# CATS_GS-Radio_MCU.net
KiCad netlist of a schematic drawn in Altium Designer
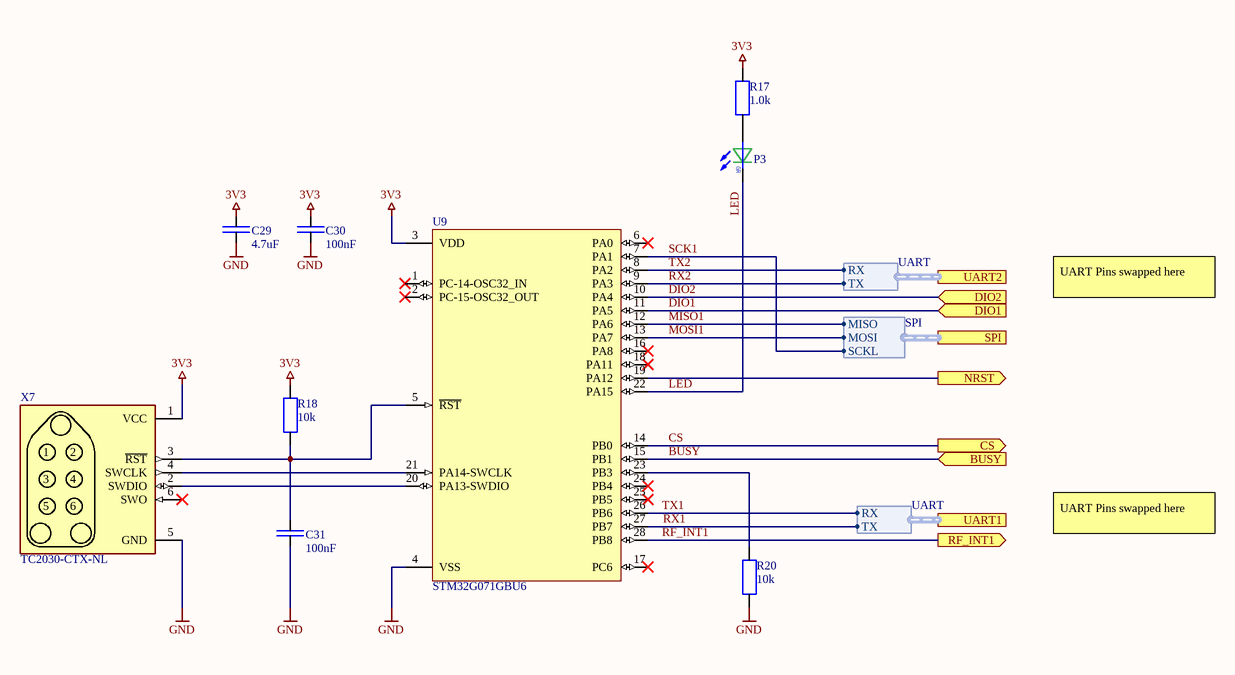
[diagram p0: CATS_GS-Radio_MCU.SchDoc]

(export (version "E")
  (design (tool "Eeschema 10.0.6"))
  (components
    (comp (ref "C29")
      (value "4.7uF")
      (footprint "SMD Keramikkondensator 0402")
      (description "SMD Ceramic Capacitor E6")
      (libsource (lib "CATS-EUROC") (part "E6 - 4.7uF"))
    )
    (comp (ref "C30")
      (value "100nF")
      (footprint "SMD Keramikkondensator 0402")
      (description "SMD Ceramic Capacitor E6")
      (libsource (lib "CATS-EUROC") (part "E6 - 100nF"))
    )
    (comp (ref "C31")
      (value "100nF")
      (footprint "SMD Keramikkondensator 0402")
      (description "SMD Ceramic Capacitor E6")
      (libsource (lib "CATS-EUROC") (part "E6 - 100nF"))
    )
    (comp (ref "P3")
      (value "LED")
      (footprint "SMD LED 0603")
      (description "Color LED")
      (libsource (lib "Diodes") (part "LED"))
    )
    (comp (ref "R17")
      (value "1.0k")
      (footprint "SMD Widerstand 0402")
      (description "SMD Chip Resistor E24")
      (libsource (lib "CATS-EUROC") (part "E24 - 1.0k"))
    )
    (comp (ref "R18")
      (value "10k")
      (footprint "SMD Widerstand 0402")
      (description "SMD Chip Resistor E24")
      (libsource (lib "CATS-EUROC") (part "E24 - 10k"))
    )
    (comp (ref "R20")
      (value "10k")
      (footprint "SMD Widerstand 0402")
      (description "SMD Chip Resistor E24")
      (libsource (lib "CATS-EUROC") (part "E24 - 10k"))
    )
    (comp (ref "U9")
      (value "STM32G071GBU6")
      (footprint "SMD IC QFN-28 4x4 0.5 Pitch")
      (description "ARM® Cortex®-M0+ series Microcontroller IC 32-Bit 64MHz 128KB (128K x 8) FLASH 28-UFQFPN (4x4)")
      (libsource (lib "Microcontrollers") (part "STM32G071GBU6"))
    )
    (comp (ref "X7")
      (value "TC2030-CTX-NL")
      (footprint "SMD Connector TC2030")
      (description "Tag-Connect for ARM-Cortex (6-Pin)")
      (libsource (lib "Connectors") (part "TC2030-CTX-NL"))
    )
  )
  (nets
    (net (code "3") (name "/BUSY") (class "Default")
      (node (ref "U9") (pin "15") (pinfunction "PB1_15") (pintype "bidirectional"))
    )
    (net (code "4") (name "/CS") (class "Default")
      (node (ref "U9") (pin "14") (pinfunction "PB0_14") (pintype "bidirectional"))
    )
    (net (code "5") (name "/DIO1") (class "Default")
      (node (ref "U9") (pin "11") (pinfunction "PA5_11") (pintype "bidirectional"))
    )
    (net (code "6") (name "/DIO2") (class "Default")
      (node (ref "U9") (pin "10") (pinfunction "PA4_10") (pintype "bidirectional"))
    )
    (net (code "7") (name "/LED") (class "Default")
      (node (ref "P3") (pin "K") (pinfunction "K_K") (pintype "passive"))
      (node (ref "U9") (pin "22") (pinfunction "PA15_22") (pintype "bidirectional"))
    )
    (net (code "8") (name "/MISO1") (class "Default")
      (node (ref "U9") (pin "12") (pinfunction "PA6_12") (pintype "bidirectional"))
    )
    (net (code "9") (name "/MOSI1") (class "Default")
      (node (ref "U9") (pin "13") (pinfunction "PA7_13") (pintype "bidirectional"))
    )
    (net (code "10") (name "/NRST") (class "Default")
      (node (ref "U9") (pin "19") (pinfunction "PA12_19") (pintype "bidirectional"))
    )
    (net (code "11") (name "/RF_INT1") (class "Default")
      (node (ref "U9") (pin "28") (pinfunction "PB8_28") (pintype "bidirectional"))
    )
    (net (code "12") (name "/RX1") (class "Default")
      (node (ref "U9") (pin "27") (pinfunction "PB7_27") (pintype "bidirectional"))
    )
    (net (code "13") (name "/RX2") (class "Default")
      (node (ref "U9") (pin "9") (pinfunction "PA3_9") (pintype "bidirectional"))
    )
    (net (code "14") (name "/SCK1") (class "Default")
      (node (ref "U9") (pin "7") (pinfunction "PA1_7") (pintype "bidirectional"))
    )
    (net (code "15") (name "/TX1") (class "Default")
      (node (ref "U9") (pin "26") (pinfunction "PB6_26") (pintype "bidirectional"))
    )
    (net (code "16") (name "/TX2") (class "Default")
      (node (ref "U9") (pin "8") (pinfunction "PA2_8") (pintype "bidirectional"))
    )
    (net (code "19") (name "3V3") (class "Default")
      (node (ref "C29") (pin "2") (pinfunction "2_2") (pintype "passive"))
      (node (ref "C30") (pin "2") (pinfunction "2_2") (pintype "passive"))
      (node (ref "R17") (pin "2") (pinfunction "2_2") (pintype "passive"))
      (node (ref "R18") (pin "2") (pinfunction "2_2") (pintype "passive"))
      (node (ref "U9") (pin "3") (pinfunction "VDD_3") (pintype "passive"))
      (node (ref "X7") (pin "1") (pinfunction "VCC_1") (pintype "power_in"))
    )
    (net (code "20") (name "GND") (class "Default")
      (node (ref "C29") (pin "1") (pinfunction "1_1") (pintype "passive"))
      (node (ref "C30") (pin "1") (pinfunction "1_1") (pintype "passive"))
      (node (ref "C31") (pin "1") (pinfunction "1_1") (pintype "passive"))
      (node (ref "R20") (pin "1") (pinfunction "1_1") (pintype "passive"))
      (node (ref "U9") (pin "4") (pinfunction "VSS_4") (pintype "passive"))
      (node (ref "X7") (pin "5") (pinfunction "GND_5") (pintype "power_in"))
    )
    (net (code "21") (name "Net-(P3-PadA)") (class "Default")
      (node (ref "P3") (pin "A") (pinfunction "A_A") (pintype "passive"))
      (node (ref "R17") (pin "1") (pinfunction "1_1") (pintype "passive"))
    )
    (net (code "22") (name "Net-(U9-PA13-SWDIO)") (class "Default")
      (node (ref "U9") (pin "20") (pinfunction "PA13-SWDIO_20") (pintype "bidirectional"))
      (node (ref "X7") (pin "2") (pinfunction "SWDIO_2") (pintype "bidirectional"))
    )
    (net (code "23") (name "Net-(U9-PA14-SWCLK)") (class "Default")
      (node (ref "U9") (pin "21") (pinfunction "PA14-SWCLK_21") (pintype "input"))
      (node (ref "X7") (pin "4") (pinfunction "SWCLK_4") (pintype "output"))
    )
    (net (code "24") (name "Net-(U9-PB3)") (class "Default")
      (node (ref "R20") (pin "2") (pinfunction "2_2") (pintype "passive"))
      (node (ref "U9") (pin "23") (pinfunction "PB3_23") (pintype "bidirectional"))
    )
    (net (code "25") (name "Net-(U9-~{RST})") (class "Default")
      (node (ref "C31") (pin "2") (pinfunction "2_2") (pintype "passive"))
      (node (ref "R18") (pin "1") (pinfunction "1_1") (pintype "passive"))
      (node (ref "U9") (pin "5") (pinfunction "~{RST}_5") (pintype "input"))
      (node (ref "X7") (pin "3") (pinfunction "~{RST}_3") (pintype "output"))
    )
    (net (code "26") (name "unconnected-(U9-PA0-Pad6)") (class "Default")
      (node (ref "U9") (pin "6") (pinfunction "PA0_6") (pintype "bidirectional+no_connect"))
    )
    (net (code "27") (name "unconnected-(U9-PA8-Pad16)") (class "Default")
      (node (ref "U9") (pin "16") (pinfunction "PA8_16") (pintype "bidirectional+no_connect"))
    )
    (net (code "28") (name "unconnected-(U9-PA11-Pad18)") (class "Default")
      (node (ref "U9") (pin "18") (pinfunction "PA11_18") (pintype "bidirectional+no_connect"))
    )
    (net (code "29") (name "unconnected-(U9-PB4-Pad24)") (class "Default")
      (node (ref "U9") (pin "24") (pinfunction "PB4_24") (pintype "bidirectional+no_connect"))
    )
    (net (code "30") (name "unconnected-(U9-PB5-Pad25)") (class "Default")
      (node (ref "U9") (pin "25") (pinfunction "PB5_25") (pintype "bidirectional+no_connect"))
    )
    (net (code "31") (name "unconnected-(U9-PC-14-OSC32_IN-Pad1)") (class "Default")
      (node (ref "U9") (pin "1") (pinfunction "PC-14-OSC32_IN_1") (pintype "bidirectional+no_connect"))
    )
    (net (code "32") (name "unconnected-(U9-PC-15-OSC32_OUT-Pad2)") (class "Default")
      (node (ref "U9") (pin "2") (pinfunction "PC-15-OSC32_OUT_2") (pintype "bidirectional+no_connect"))
    )
    (net (code "33") (name "unconnected-(U9-PC6-Pad17)") (class "Default")
      (node (ref "U9") (pin "17") (pinfunction "PC6_17") (pintype "bidirectional+no_connect"))
    )
    (net (code "34") (name "unconnected-(X7-SWO-Pad6)") (class "Default")
      (node (ref "X7") (pin "6") (pinfunction "SWO_6") (pintype "input+no_connect"))
    )
  )
)
